# Accelerometer.net
KiCad netlist of a schematic drawn in Altium Designer
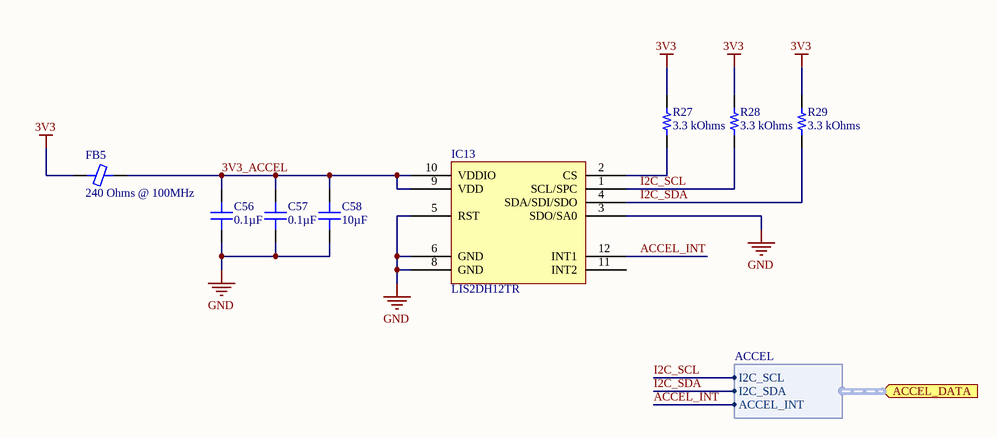
[diagram p0: Accelerometer.SchDoc]

(export (version "E")
  (design (tool "Eeschema 10.0.6"))
  (components
    (comp (ref "C56")
      (value "0.1µF")
      (footprint "CAP 0201_0603")
      (description "CAP CER 0.1UF 16V X5R 0201")
      (fields
        (field (name "PART NUMBER") "GRM033R61C104ME84D")
        (field (name "MANUFACTURER") "Murata Electronics")
      )
      (libsource (lib "Celestial Altium Library - altium_library") (part "Capacitor"))
    )
    (comp (ref "C57")
      (value "0.1µF")
      (footprint "CAP 0201_0603")
      (description "CAP CER 0.1UF 16V X5R 0201")
      (fields
        (field (name "PART NUMBER") "GRM033R61C104ME84D")
        (field (name "MANUFACTURER") "Murata Electronics")
      )
      (libsource (lib "Celestial Altium Library - altium_library") (part "Capacitor"))
    )
    (comp (ref "C58")
      (value "10µF")
      (footprint "CAP 0603_1608")
      (description "CAP CER 10UF 10V X5R 0603")
      (fields (field (name "PART NUMBER") "LMK107BBJ106KALT") (field (name "MANUFACTURER") "Taiyo Yuden"))
      (libsource (lib "Celestial Altium Library - altium_library") (part "Capacitor"))
    )
    (comp (ref "FB5")
      (value "240 Ohms @ 100MHz")
      (footprint "FER 0201_0603")
      (description "FERRITE BEAD 240 OHM 0201 1LN")
      (fields (field (name "PART NUMBER") "BK0603TS241-T") (field (name "MANUFACTURER") "Taiyo Yuden"))
      (libsource (lib "Celestial Altium Library - altium_library") (part "Ferrite Chip"))
    )
    (comp (ref "IC13")
      (value "LIS2DH12TR")
      (footprint "ST LGA-12 2x2MM")
      (description "ACCEL 2-16G I2C/SPI 12LGA")
      (fields (field (name "MANUFACTURER") "STMicroelectronics"))
      (libsource (lib "Celestial Altium Library - altium_library") (part "ST LIS2DH12TR"))
    )
    (comp (ref "R27")
      (value "3.3 kOhms")
      (footprint "RES 0201_0603")
      (description "RES SMD 3.3K OHM 1% 1/20W 0201")
      (fields
        (field (name "PART NUMBER") "ERJ-1GNF3301C")
        (field (name "MANUFACTURER") "Panasonic Electronic Components")
      )
      (libsource (lib "Celestial Altium Library - altium_library") (part "Resistor"))
    )
    (comp (ref "R28")
      (value "3.3 kOhms")
      (footprint "RES 0201_0603")
      (description "RES SMD 3.3K OHM 1% 1/20W 0201")
      (fields
        (field (name "PART NUMBER") "ERJ-1GNF3301C")
        (field (name "MANUFACTURER") "Panasonic Electronic Components")
      )
      (libsource (lib "Celestial Altium Library - altium_library") (part "Resistor"))
    )
    (comp (ref "R29")
      (value "3.3 kOhms")
      (footprint "RES 0201_0603")
      (description "RES SMD 3.3K OHM 1% 1/20W 0201")
      (fields
        (field (name "PART NUMBER") "ERJ-1GNF3301C")
        (field (name "MANUFACTURER") "Panasonic Electronic Components")
      )
      (libsource (lib "Celestial Altium Library - altium_library") (part "Resistor"))
    )
  )
  (nets
    (net (code "2") (name "/3V3_ACCEL") (class "Default")
      (node (ref "C56") (pin "2") (pinfunction "2_2") (pintype "passive"))
      (node (ref "C57") (pin "2") (pinfunction "2_2") (pintype "passive"))
      (node (ref "C58") (pin "2") (pinfunction "2_2") (pintype "passive"))
      (node (ref "FB5") (pin "2") (pinfunction "2_2") (pintype "passive"))
      (node (ref "IC13") (pin "10") (pinfunction "VDDIO_10") (pintype "passive"))
      (node (ref "IC13") (pin "9") (pinfunction "VDD_9") (pintype "passive"))
    )
    (net (code "3") (name "/ACCEL_INT") (class "Default")
      (node (ref "IC13") (pin "12") (pinfunction "INT1_12") (pintype "passive"))
    )
    (net (code "4") (name "/I2C_SCL") (class "Default")
      (node (ref "IC13") (pin "1") (pinfunction "SCL/SPC_1") (pintype "passive"))
      (node (ref "R28") (pin "1") (pinfunction "1_1") (pintype "passive"))
    )
    (net (code "5") (name "/I2C_SDA") (class "Default")
      (node (ref "IC13") (pin "4") (pinfunction "SDA/SDI/SDO_4") (pintype "passive"))
      (node (ref "R29") (pin "1") (pinfunction "1_1") (pintype "passive"))
    )
    (net (code "7") (name "3V3") (class "Default")
      (node (ref "FB5") (pin "1") (pinfunction "1_1") (pintype "passive"))
      (node (ref "R27") (pin "2") (pinfunction "2_2") (pintype "passive"))
      (node (ref "R28") (pin "2") (pinfunction "2_2") (pintype "passive"))
      (node (ref "R29") (pin "2") (pinfunction "2_2") (pintype "passive"))
    )
    (net (code "8") (name "GND") (class "Default")
      (node (ref "C56") (pin "1") (pinfunction "1_1") (pintype "passive"))
      (node (ref "C57") (pin "1") (pinfunction "1_1") (pintype "passive"))
      (node (ref "C58") (pin "1") (pinfunction "1_1") (pintype "passive"))
      (node (ref "IC13") (pin "3") (pinfunction "SDO/SA0_3") (pintype "passive"))
      (node (ref "IC13") (pin "5") (pinfunction "RST_5") (pintype "passive"))
      (node (ref "IC13") (pin "6") (pinfunction "GND_6") (pintype "passive"))
      (node (ref "IC13") (pin "8") (pinfunction "GND_8") (pintype "passive"))
    )
    (net (code "9") (name "Net-(IC13-CS)") (class "Default")
      (node (ref "IC13") (pin "2") (pinfunction "CS_2") (pintype "passive"))
      (node (ref "R27") (pin "1") (pinfunction "1_1") (pintype "passive"))
    )
    (net (code "10") (name "unconnected-(IC13-INT2-Pad11)") (class "Default")
      (node (ref "IC13") (pin "11") (pinfunction "INT2_11") (pintype "passive"))
    )
  )
)
